# PIClab1.net
KiCad netlist of a schematic drawn in EAGLE
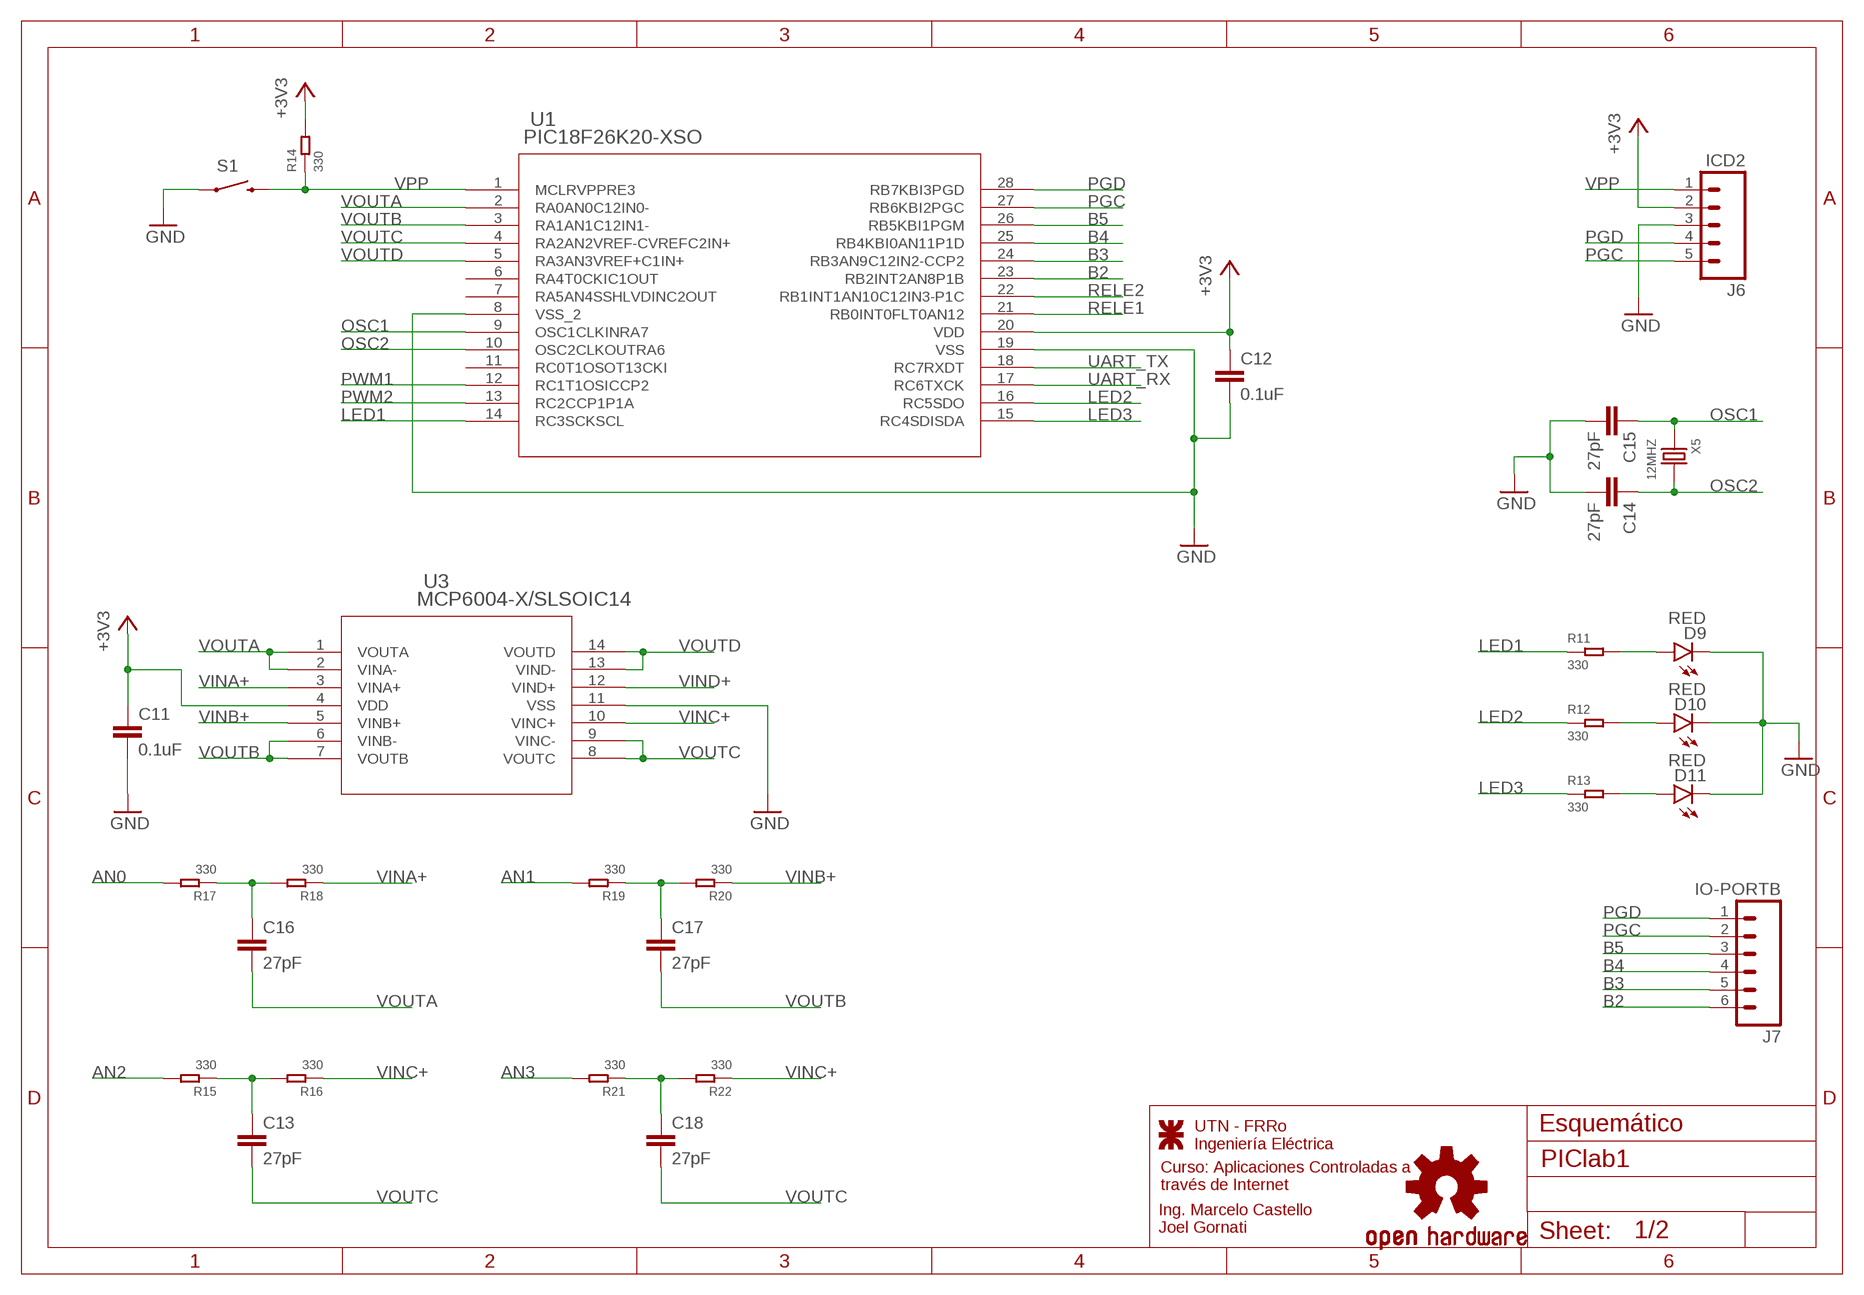
[diagram p0: schematic, sheet 1]
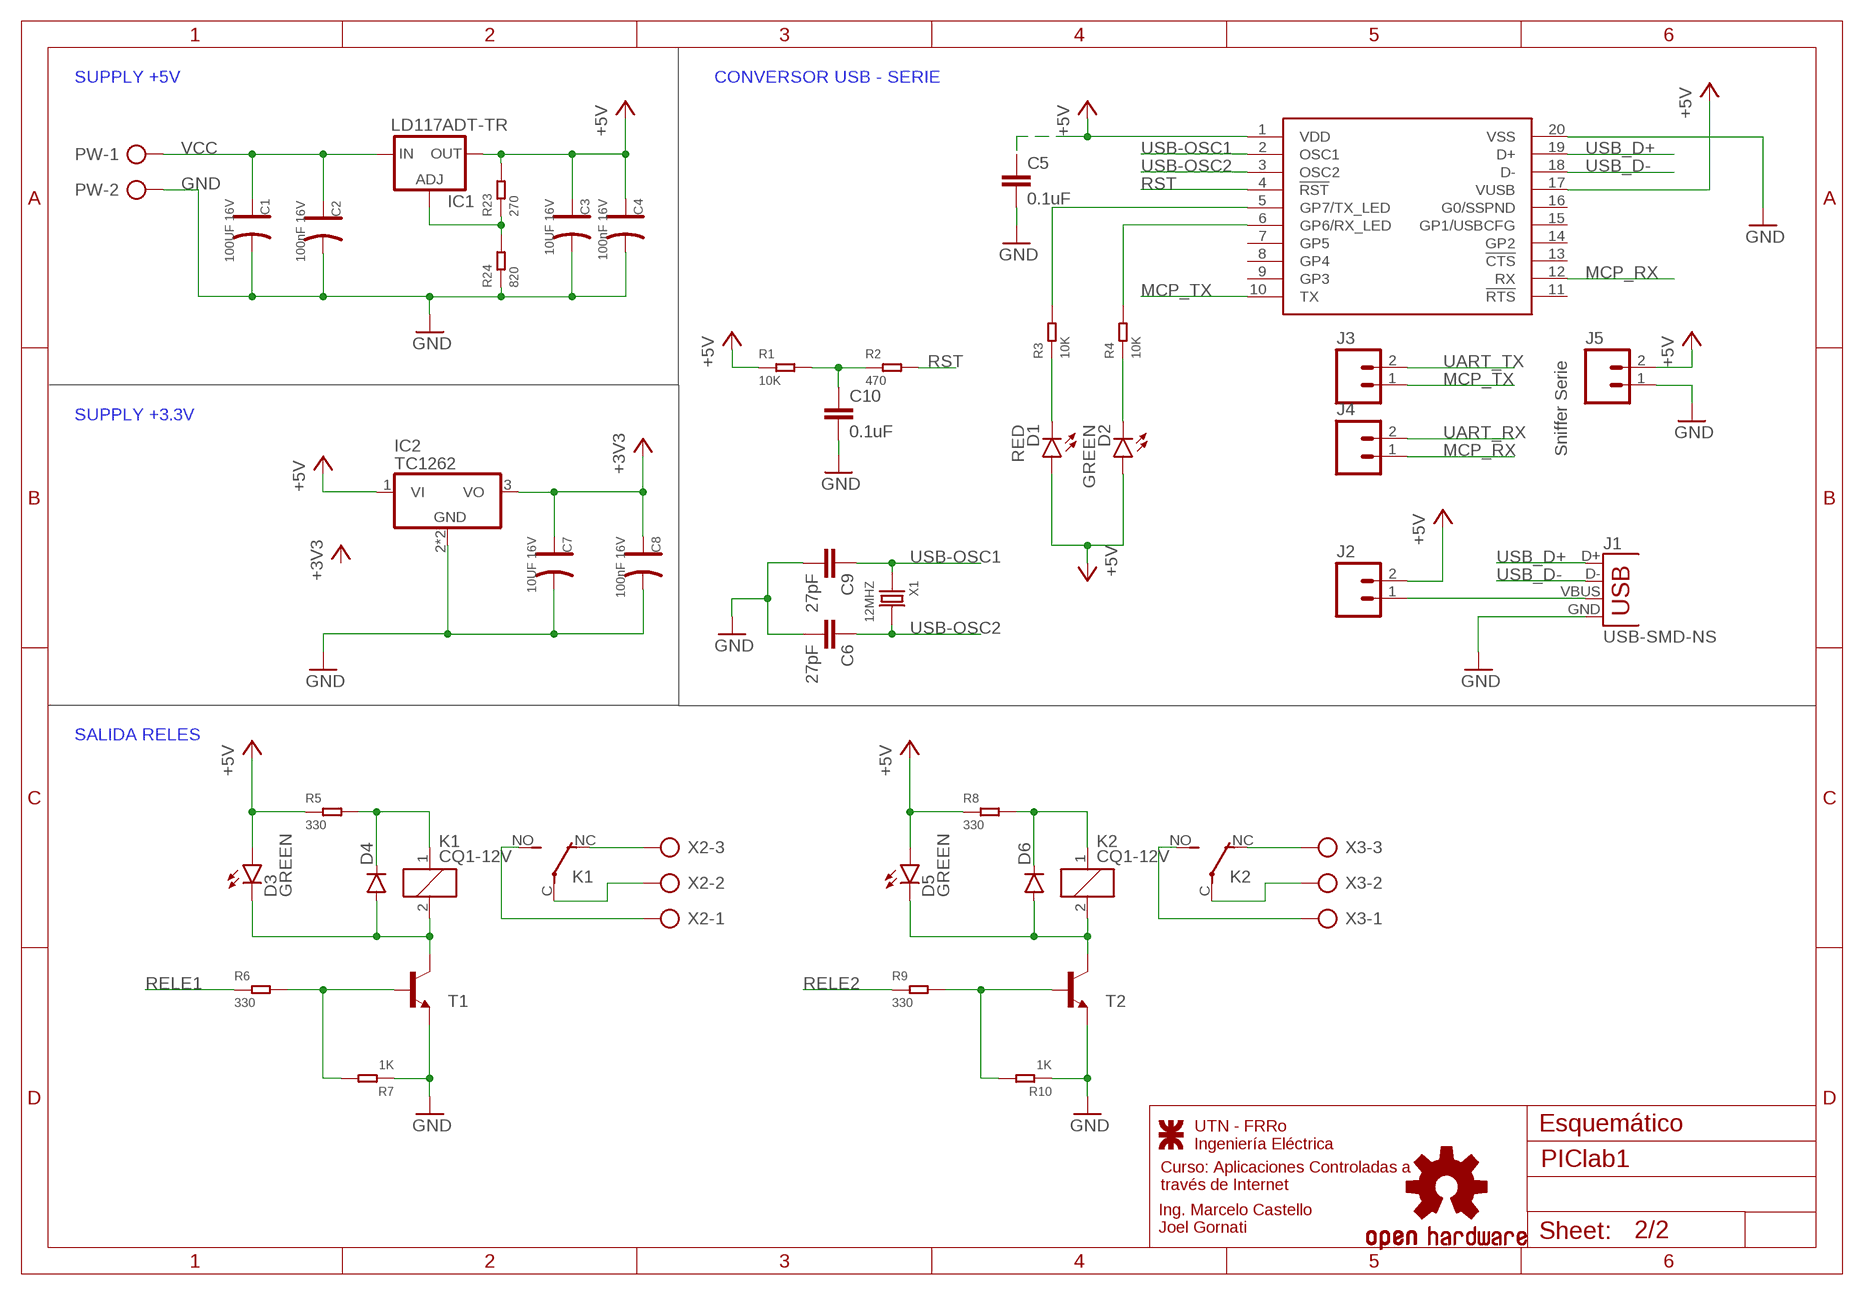
[diagram p1: schematic, sheet 2]

(export (version "E")
  (design (tool "Eeschema 10.0.6"))
  (components
    (comp (ref "C1")
      (value "100UF 16V")
      (footprint "eagle-import:ELECTRO-SMD-A-3.8MM")
      (libsource (lib "eagle-import") (part "ALUMINUM-SMD-10UF-16V"))
    )
    (comp (ref "C2")
      (value "100nF 16V")
      (footprint "eagle-import:ELECTRO-SMD-A-3.8MM")
      (libsource (lib "eagle-import") (part "ALUMINUM-SMD-10UF-16V"))
    )
    (comp (ref "C3")
      (value "10UF 16V")
      (footprint "eagle-import:ELECTRO-SMD-A-3.8MM")
      (libsource (lib "eagle-import") (part "ALUMINUM-SMD-10UF-16V"))
    )
    (comp (ref "C4")
      (value "100nF 16V")
      (footprint "eagle-import:ELECTRO-SMD-A-3.8MM")
      (libsource (lib "eagle-import") (part "ALUMINUM-SMD-10UF-16V"))
    )
    (comp (ref "C5")
      (value "0.1uF")
      (footprint "eagle-import:1206")
      (libsource (lib "eagle-import") (part "CAP1206"))
    )
    (comp (ref "C6")
      (value "27pF")
      (footprint "eagle-import:1206")
      (libsource (lib "eagle-import") (part "CAP1206"))
    )
    (comp (ref "C7")
      (value "10UF 16V")
      (footprint "eagle-import:ELECTRO-SMD-A-3.8MM")
      (libsource (lib "eagle-import") (part "ALUMINUM-SMD-10UF-16V"))
    )
    (comp (ref "C8")
      (value "100nF 16V")
      (footprint "eagle-import:ELECTRO-SMD-A-3.8MM")
      (libsource (lib "eagle-import") (part "ALUMINUM-SMD-10UF-16V"))
    )
    (comp (ref "C9")
      (value "27pF")
      (footprint "eagle-import:1206")
      (libsource (lib "eagle-import") (part "CAP1206"))
    )
    (comp (ref "C10")
      (value "0.1uF")
      (footprint "eagle-import:1206")
      (libsource (lib "eagle-import") (part "CAP1206"))
    )
    (comp (ref "D1")
      (value "RED")
      (footprint "eagle-import:LED-1206")
      (libsource (lib "eagle-import") (part "LED-REDLILYPAD"))
    )
    (comp (ref "D2")
      (value "GREEN")
      (footprint "eagle-import:LED-1206")
      (libsource (lib "eagle-import") (part "LED-REDLILYPAD"))
    )
    (comp (ref "D3")
      (value "GREEN")
      (footprint "eagle-import:LED-1206")
      (libsource (lib "eagle-import") (part "LED-REDLILYPAD"))
    )
    (comp (ref "D4")
      (value "DIODEHV")
      (footprint "eagle-import:DIODE-HV")
      (libsource (lib "eagle-import") (part "DIODEHV"))
    )
    (comp (ref "D5")
      (value "GREEN")
      (footprint "eagle-import:LED-1206")
      (libsource (lib "eagle-import") (part "LED-REDLILYPAD"))
    )
    (comp (ref "D6")
      (value "DIODEHV")
      (footprint "eagle-import:DIODE-HV")
      (libsource (lib "eagle-import") (part "DIODEHV"))
    )
    (comp (ref "IC1")
      (value "LD117ADT-TR")
      (footprint "eagle-import:DPACK")
      (libsource (lib "eagle-import") (part "LD117A?DT-TR"))
    )
    (comp (ref "IC2")
      (value "TC1262")
      (footprint "eagle-import:SOT223")
      (libsource (lib "eagle-import") (part "TC1262"))
    )
    (comp (ref "J1")
      (value "USB-SMD-NS")
      (footprint "eagle-import:USB-MINIB-NOSTOP")
      (libsource (lib "eagle-import") (part "USB-SMD-NS"))
    )
    (comp (ref "J2")
      (value "M02PTH")
      (footprint "eagle-import:1X02")
      (libsource (lib "eagle-import") (part "M02PTH"))
    )
    (comp (ref "J3")
      (value "M02PTH")
      (footprint "eagle-import:1X02")
      (libsource (lib "eagle-import") (part "M02PTH"))
    )
    (comp (ref "J4")
      (value "M02PTH")
      (footprint "eagle-import:1X02")
      (libsource (lib "eagle-import") (part "M02PTH"))
    )
    (comp (ref "J5")
      (value "M02PTH")
      (footprint "eagle-import:1X02")
      (libsource (lib "eagle-import") (part "M02PTH"))
    )
    (comp (ref "K1")
      (value "CQ1-12V")
      (footprint "eagle-import:CQ1")
      (libsource (lib "eagle-import") (part "CQ1-12V"))
    )
    (comp (ref "K2")
      (value "CQ1-12V")
      (footprint "eagle-import:CQ1")
      (libsource (lib "eagle-import") (part "CQ1-12V"))
    )
    (comp (ref "LOGO1")
      (value "OSHW-LOGOMINI")
      (footprint "eagle-import:OSHW-LOGO-MINI")
      (libsource (lib "eagle-import") (part "OSHW-LOGOMINI"))
    )
    (comp (ref "PW")
      (value "AK300/2")
      (footprint "eagle-import:AK300_2")
      (libsource (lib "eagle-import") (part "AK300/2"))
    )
    (comp (ref "R1")
      (value "10K")
      (footprint "eagle-import:R1206")
      (libsource (lib "eagle-import") (part "RES-1206"))
    )
    (comp (ref "R2")
      (value "470")
      (footprint "eagle-import:R1206")
      (libsource (lib "eagle-import") (part "RES-1206"))
    )
    (comp (ref "R3")
      (value "10K")
      (footprint "eagle-import:R1206")
      (libsource (lib "eagle-import") (part "RES-1206"))
    )
    (comp (ref "R4")
      (value "10K")
      (footprint "eagle-import:R1206")
      (libsource (lib "eagle-import") (part "RES-1206"))
    )
    (comp (ref "R5")
      (value "330")
      (footprint "eagle-import:R1206")
      (libsource (lib "eagle-import") (part "RES-1206"))
    )
    (comp (ref "R6")
      (value "330")
      (footprint "eagle-import:R1206")
      (libsource (lib "eagle-import") (part "RES-1206"))
    )
    (comp (ref "R7")
      (value "1K")
      (footprint "eagle-import:R1206")
      (libsource (lib "eagle-import") (part "RES-1206"))
    )
    (comp (ref "R8")
      (value "330")
      (footprint "eagle-import:R1206")
      (libsource (lib "eagle-import") (part "RES-1206"))
    )
    (comp (ref "R9")
      (value "330")
      (footprint "eagle-import:R1206")
      (libsource (lib "eagle-import") (part "RES-1206"))
    )
    (comp (ref "R10")
      (value "1K")
      (footprint "eagle-import:R1206")
      (libsource (lib "eagle-import") (part "RES-1206"))
    )
    (comp (ref "R23")
      (value "270")
      (footprint "eagle-import:R1206")
      (libsource (lib "eagle-import") (part "RES-1206"))
    )
    (comp (ref "R24")
      (value "820")
      (footprint "eagle-import:R1206")
      (libsource (lib "eagle-import") (part "RES-1206"))
    )
    (comp (ref "T1")
      (value "BC817-25-NPN-SOT23-BEC")
      (footprint "eagle-import:SOT23-BEC")
      (libsource (lib "eagle-import") (part "-NPN-SOT23-BECBC817-25"))
    )
    (comp (ref "T2")
      (value "BC817-25-NPN-SOT23-BEC")
      (footprint "eagle-import:SOT23-BEC")
      (libsource (lib "eagle-import") (part "-NPN-SOT23-BECBC817-25"))
    )
    (comp (ref "U$2")
      (value "UTNLOGO")
      (footprint "eagle-import:UTNLOGO")
      (libsource (lib "eagle-import") (part "UTNLOGO"))
    )
    (comp (ref "U2")
      (value "MCP2200SOIC")
      (footprint "eagle-import:MCP2200")
      (libsource (lib "eagle-import") (part "MCP2200SOIC"))
    )
    (comp (ref "X1")
      (value "12MHZ")
      (footprint "eagle-import:HC49UP")
      (libsource (lib "eagle-import") (part "CRYSTAL'HC49UP'"))
    )
    (comp (ref "X2")
      (value "AK500/3")
      (footprint "eagle-import:AK500_3")
      (libsource (lib "eagle-import") (part "AK500/3"))
    )
    (comp (ref "X3")
      (value "AK500/3")
      (footprint "eagle-import:AK500_3")
      (libsource (lib "eagle-import") (part "AK500/3"))
    )
    (comp (ref "C11")
      (value "0.1uF")
      (footprint "eagle-import:1206")
      (libsource (lib "eagle-import") (part "CAP1206"))
    )
    (comp (ref "C12")
      (value "0.1uF")
      (footprint "eagle-import:1206")
      (libsource (lib "eagle-import") (part "CAP1206"))
    )
    (comp (ref "C13")
      (value "27pF")
      (footprint "eagle-import:1206")
      (libsource (lib "eagle-import") (part "CAP1206"))
    )
    (comp (ref "C14")
      (value "27pF")
      (footprint "eagle-import:1206")
      (libsource (lib "eagle-import") (part "CAP1206"))
    )
    (comp (ref "C15")
      (value "27pF")
      (footprint "eagle-import:1206")
      (libsource (lib "eagle-import") (part "CAP1206"))
    )
    (comp (ref "C16")
      (value "27pF")
      (footprint "eagle-import:1206")
      (libsource (lib "eagle-import") (part "CAP1206"))
    )
    (comp (ref "C17")
      (value "27pF")
      (footprint "eagle-import:1206")
      (libsource (lib "eagle-import") (part "CAP1206"))
    )
    (comp (ref "C18")
      (value "27pF")
      (footprint "eagle-import:1206")
      (libsource (lib "eagle-import") (part "CAP1206"))
    )
    (comp (ref "D9")
      (value "RED")
      (footprint "eagle-import:LED-1206")
      (libsource (lib "eagle-import") (part "LED-REDLILYPAD"))
    )
    (comp (ref "D10")
      (value "RED")
      (footprint "eagle-import:LED-1206")
      (libsource (lib "eagle-import") (part "LED-REDLILYPAD"))
    )
    (comp (ref "D11")
      (value "RED")
      (footprint "eagle-import:LED-1206")
      (libsource (lib "eagle-import") (part "LED-REDLILYPAD"))
    )
    (comp (ref "J6")
      (value "ICD2")
      (footprint "eagle-import:1X05")
      (libsource (lib "eagle-import") (part "M05PTH"))
    )
    (comp (ref "J7")
      (value "IO-PORTB")
      (footprint "eagle-import:1X06")
      (libsource (lib "eagle-import") (part "M06SILK_FEMALE_PTH"))
    )
    (comp (ref "LOGO2")
      (value "OSHW-LOGOMINI")
      (footprint "eagle-import:OSHW-LOGO-MINI")
      (libsource (lib "eagle-import") (part "OSHW-LOGOMINI"))
    )
    (comp (ref "R11")
      (value "330")
      (footprint "eagle-import:R1206")
      (libsource (lib "eagle-import") (part "RES-1206"))
    )
    (comp (ref "R12")
      (value "330")
      (footprint "eagle-import:R1206")
      (libsource (lib "eagle-import") (part "RES-1206"))
    )
    (comp (ref "R13")
      (value "330")
      (footprint "eagle-import:R1206")
      (libsource (lib "eagle-import") (part "RES-1206"))
    )
    (comp (ref "R14")
      (value "330")
      (footprint "eagle-import:R1206")
      (libsource (lib "eagle-import") (part "RES-1206"))
    )
    (comp (ref "R15")
      (value "330")
      (footprint "eagle-import:R1206")
      (libsource (lib "eagle-import") (part "RES-1206"))
    )
    (comp (ref "R16")
      (value "330")
      (footprint "eagle-import:R1206")
      (libsource (lib "eagle-import") (part "RES-1206"))
    )
    (comp (ref "R17")
      (value "330")
      (footprint "eagle-import:R1206")
      (libsource (lib "eagle-import") (part "RES-1206"))
    )
    (comp (ref "R18")
      (value "330")
      (footprint "eagle-import:R1206")
      (libsource (lib "eagle-import") (part "RES-1206"))
    )
    (comp (ref "R19")
      (value "330")
      (footprint "eagle-import:R1206")
      (libsource (lib "eagle-import") (part "RES-1206"))
    )
    (comp (ref "R20")
      (value "330")
      (footprint "eagle-import:R1206")
      (libsource (lib "eagle-import") (part "RES-1206"))
    )
    (comp (ref "R21")
      (value "330")
      (footprint "eagle-import:R1206")
      (libsource (lib "eagle-import") (part "RES-1206"))
    )
    (comp (ref "R22")
      (value "330")
      (footprint "eagle-import:R1206")
      (libsource (lib "eagle-import") (part "RES-1206"))
    )
    (comp (ref "S1")
      (value "SWITCH-MOMENTARY-2SMD-4")
      (footprint "eagle-import:TACTILE_SWITCH_TALL")
      (libsource (lib "eagle-import") (part "SWITCH-MOMENTARY-2SMD-4"))
    )
    (comp (ref "U$3")
      (value "UTNLOGO")
      (footprint "eagle-import:UTNLOGO")
      (libsource (lib "eagle-import") (part "UTNLOGO"))
    )
    (comp (ref "U1")
      (value "PIC18F26K20-XSO")
      (footprint "eagle-import:SOIC28-W_MC")
      (libsource (lib "eagle-import") (part "PIC18F26K20-XSO"))
    )
    (comp (ref "U3")
      (value "MCP6004-X/SLSOIC14")
      (footprint "eagle-import:SOIC14-N_MC")
      (libsource (lib "eagle-import") (part "MCP6004-X/SLSOIC14"))
    )
    (comp (ref "X5")
      (value "12MHZ")
      (footprint "eagle-import:HC49UP")
      (libsource (lib "eagle-import") (part "CRYSTAL'HC49UP'"))
    )
  )
  (nets
    (net (code "1") (name "+3V3") (class "Default")
      (node (ref "C11") (pin "1") (pinfunction "1_1") (pintype "passive"))
      (node (ref "C12") (pin "1") (pinfunction "1_1") (pintype "passive"))
      (node (ref "C7") (pin "+") (pinfunction "+_+") (pintype "passive"))
      (node (ref "C8") (pin "+") (pinfunction "+_+") (pintype "passive"))
      (node (ref "IC2") (pin "3") (pinfunction "VO_3") (pintype "passive"))
      (node (ref "J6") (pin "2") (pinfunction "2_2") (pintype "passive"))
      (node (ref "R14") (pin "2") (pinfunction "2_2") (pintype "passive"))
      (node (ref "U1") (pin "20") (pinfunction "VDD_20") (pintype "passive"))
      (node (ref "U3") (pin "4") (pinfunction "VDD_4") (pintype "passive"))
    )
    (net (code "2") (name "+5V") (class "Default")
      (node (ref "C3") (pin "+") (pinfunction "+_+") (pintype "passive"))
      (node (ref "C4") (pin "+") (pinfunction "+_+") (pintype "passive"))
      (node (ref "C5") (pin "1") (pinfunction "1_1") (pintype "passive"))
      (node (ref "D1") (pin "A") (pinfunction "A_A") (pintype "passive"))
      (node (ref "D2") (pin "A") (pinfunction "A_A") (pintype "passive"))
      (node (ref "D3") (pin "A") (pinfunction "A_A") (pintype "passive"))
      (node (ref "D5") (pin "A") (pinfunction "A_A") (pintype "passive"))
      (node (ref "IC1") (pin "4") (pinfunction "OUT_4") (pintype "passive"))
      (node (ref "IC2") (pin "1") (pinfunction "VI_1") (pintype "input"))
      (node (ref "J2") (pin "2") (pinfunction "2_2") (pintype "passive"))
      (node (ref "J5") (pin "2") (pinfunction "2_2") (pintype "passive"))
      (node (ref "R1") (pin "1") (pinfunction "1_1") (pintype "passive"))
      (node (ref "R23") (pin "2") (pinfunction "2_2") (pintype "passive"))
      (node (ref "R5") (pin "1") (pinfunction "1_1") (pintype "passive"))
      (node (ref "R8") (pin "1") (pinfunction "1_1") (pintype "passive"))
      (node (ref "U2") (pin "1") (pinfunction "VDD_1") (pintype "bidirectional"))
      (node (ref "U2") (pin "17") (pinfunction "VUSB_17") (pintype "bidirectional"))
    )
    (net (code "3") (name "AN0") (class "Default")
      (node (ref "R17") (pin "2") (pinfunction "2_2") (pintype "passive"))
    )
    (net (code "4") (name "AN1") (class "Default")
      (node (ref "R19") (pin "2") (pinfunction "2_2") (pintype "passive"))
    )
    (net (code "5") (name "AN2") (class "Default")
      (node (ref "R15") (pin "2") (pinfunction "2_2") (pintype "passive"))
    )
    (net (code "6") (name "AN3") (class "Default")
      (node (ref "R21") (pin "2") (pinfunction "2_2") (pintype "passive"))
    )
    (net (code "7") (name "B2") (class "Default")
      (node (ref "J7") (pin "6") (pinfunction "6_6") (pintype "passive"))
      (node (ref "U1") (pin "23") (pinfunction "RB2INT2AN8P1B_23") (pintype "passive"))
    )
    (net (code "8") (name "B3") (class "Default")
      (node (ref "J7") (pin "5") (pinfunction "5_5") (pintype "passive"))
      (node (ref "U1") (pin "24") (pinfunction "RB3AN9C12IN2-CCP2_24") (pintype "passive"))
    )
    (net (code "9") (name "B4") (class "Default")
      (node (ref "J7") (pin "4") (pinfunction "4_4") (pintype "passive"))
      (node (ref "U1") (pin "25") (pinfunction "RB4KBI0AN11P1D_25") (pintype "passive"))
    )
    (net (code "10") (name "B5") (class "Default")
      (node (ref "J7") (pin "3") (pinfunction "3_3") (pintype "passive"))
      (node (ref "U1") (pin "26") (pinfunction "RB5KBI1PGM_26") (pintype "passive"))
    )
    (net (code "11") (name "GND") (class "Default")
      (node (ref "C1") (pin "-") (pinfunction "-_-") (pintype "passive"))
      (node (ref "C10") (pin "2") (pinfunction "2_2") (pintype "passive"))
      (node (ref "C11") (pin "2") (pinfunction "2_2") (pintype "passive"))
      (node (ref "C12") (pin "2") (pinfunction "2_2") (pintype "passive"))
      (node (ref "C14") (pin "2") (pinfunction "2_2") (pintype "passive"))
      (node (ref "C15") (pin "2") (pinfunction "2_2") (pintype "passive"))
      (node (ref "C2") (pin "-") (pinfunction "-_-") (pintype "passive"))
      (node (ref "C3") (pin "-") (pinfunction "-_-") (pintype "passive"))
      (node (ref "C4") (pin "-") (pinfunction "-_-") (pintype "passive"))
      (node (ref "C5") (pin "2") (pinfunction "2_2") (pintype "passive"))
      (node (ref "C6") (pin "2") (pinfunction "2_2") (pintype "passive"))
      (node (ref "C7") (pin "-") (pinfunction "-_-") (pintype "passive"))
      (node (ref "C8") (pin "-") (pinfunction "-_-") (pintype "passive"))
      (node (ref "C9") (pin "2") (pinfunction "2_2") (pintype "passive"))
      (node (ref "D10") (pin "C") (pinfunction "C_C") (pintype "passive"))
      (node (ref "D11") (pin "C") (pinfunction "C_C") (pintype "passive"))
      (node (ref "D9") (pin "C") (pinfunction "C_C") (pintype "passive"))
      (node (ref "IC2") (pin "2") (pinfunction "GND_2") (pintype "passive"))
      (node (ref "IC2") (pin "4") (pinfunction "GND_4") (pintype "passive"))
      (node (ref "J1") (pin "GND") (pinfunction "GND_GND") (pintype "bidirectional"))
      (node (ref "J5") (pin "1") (pinfunction "1_1") (pintype "passive"))
      (node (ref "J6") (pin "3") (pinfunction "3_3") (pintype "passive"))
      (node (ref "PW") (pin "2") (pinfunction "KL_2") (pintype "passive"))
      (node (ref "R10") (pin "1") (pinfunction "1_1") (pintype "passive"))
      (node (ref "R24") (pin "1") (pinfunction "1_1") (pintype "passive"))
      (node (ref "R7") (pin "1") (pinfunction "1_1") (pintype "passive"))
      (node (ref "S1") (pin "A2") (pinfunction "1_A2") (pintype "passive"))
      (node (ref "T1") (pin "E") (pinfunction "E_E") (pintype "passive"))
      (node (ref "T2") (pin "E") (pinfunction "E_E") (pintype "passive"))
      (node (ref "U1") (pin "19") (pinfunction "VSS_19") (pintype "passive"))
      (node (ref "U1") (pin "8") (pinfunction "VSS_2_8") (pintype "passive"))
      (node (ref "U2") (pin "20") (pinfunction "VSS_20") (pintype "bidirectional"))
      (node (ref "U3") (pin "11") (pinfunction "VSS_11") (pintype "passive"))
    )
    (net (code "12") (name "LED1") (class "Default")
      (node (ref "R11") (pin "1") (pinfunction "1_1") (pintype "passive"))
      (node (ref "U1") (pin "14") (pinfunction "RC3SCKSCL_14") (pintype "passive"))
    )
    (net (code "13") (name "LED2") (class "Default")
      (node (ref "R12") (pin "1") (pinfunction "1_1") (pintype "passive"))
      (node (ref "U1") (pin "16") (pinfunction "RC5SDO_16") (pintype "passive"))
    )
    (net (code "14") (name "LED3") (class "Default")
      (node (ref "R13") (pin "1") (pinfunction "1_1") (pintype "passive"))
      (node (ref "U1") (pin "15") (pinfunction "RC4SDISDA_15") (pintype "passive"))
    )
    (net (code "15") (name "MCP_RX") (class "Default")
      (node (ref "J4") (pin "1") (pinfunction "1_1") (pintype "passive"))
      (node (ref "U2") (pin "12") (pinfunction "RX_12") (pintype "bidirectional"))
    )
    (net (code "16") (name "MCP_TX") (class "Default")
      (node (ref "J3") (pin "1") (pinfunction "1_1") (pintype "passive"))
      (node (ref "U2") (pin "10") (pinfunction "TX_10") (pintype "bidirectional"))
    )
    (net (code "17") (name "Net-(C10-Pad1)") (class "Default")
      (node (ref "C10") (pin "1") (pinfunction "1_1") (pintype "passive"))
      (node (ref "R1") (pin "2") (pinfunction "2_2") (pintype "passive"))
      (node (ref "R2") (pin "1") (pinfunction "1_1") (pintype "passive"))
    )
    (net (code "18") (name "Net-(C13-Pad1)") (class "Default")
      (node (ref "C13") (pin "1") (pinfunction "1_1") (pintype "passive"))
      (node (ref "R15") (pin "1") (pinfunction "1_1") (pintype "passive"))
      (node (ref "R16") (pin "2") (pinfunction "2_2") (pintype "passive"))
    )
    (net (code "19") (name "Net-(C16-Pad1)") (class "Default")
      (node (ref "C16") (pin "1") (pinfunction "1_1") (pintype "passive"))
      (node (ref "R17") (pin "1") (pinfunction "1_1") (pintype "passive"))
      (node (ref "R18") (pin "2") (pinfunction "2_2") (pintype "passive"))
    )
    (net (code "20") (name "Net-(C17-Pad1)") (class "Default")
      (node (ref "C17") (pin "1") (pinfunction "1_1") (pintype "passive"))
      (node (ref "R19") (pin "1") (pinfunction "1_1") (pintype "passive"))
      (node (ref "R20") (pin "2") (pinfunction "2_2") (pintype "passive"))
    )
    (net (code "21") (name "Net-(C18-Pad1)") (class "Default")
      (node (ref "C18") (pin "1") (pinfunction "1_1") (pintype "passive"))
      (node (ref "R21") (pin "1") (pinfunction "1_1") (pintype "passive"))
      (node (ref "R22") (pin "2") (pinfunction "2_2") (pintype "passive"))
    )
    (net (code "22") (name "Net-(D1-PadC)") (class "Default")
      (node (ref "D1") (pin "C") (pinfunction "C_C") (pintype "passive"))
      (node (ref "R3") (pin "1") (pinfunction "1_1") (pintype "passive"))
    )
    (net (code "23") (name "Net-(D2-PadC)") (class "Default")
      (node (ref "D2") (pin "C") (pinfunction "C_C") (pintype "passive"))
      (node (ref "R4") (pin "1") (pinfunction "1_1") (pintype "passive"))
    )
    (net (code "24") (name "Net-(D3-PadC)") (class "Default")
      (node (ref "D3") (pin "C") (pinfunction "C_C") (pintype "passive"))
      (node (ref "D4") (pin "A") (pinfunction "A_A") (pintype "passive"))
      (node (ref "K1") (pin "2") (pinfunction "2_2") (pintype "passive"))
      (node (ref "T1") (pin "C") (pinfunction "C_C") (pintype "passive"))
    )
    (net (code "25") (name "Net-(D4-PadC)") (class "Default")
      (node (ref "D4") (pin "C") (pinfunction "C_C") (pintype "passive"))
      (node (ref "K1") (pin "1") (pinfunction "1_1") (pintype "passive"))
      (node (ref "R5") (pin "2") (pinfunction "2_2") (pintype "passive"))
    )
    (net (code "26") (name "Net-(D5-PadC)") (class "Default")
      (node (ref "D5") (pin "C") (pinfunction "C_C") (pintype "passive"))
      (node (ref "D6") (pin "A") (pinfunction "A_A") (pintype "passive"))
      (node (ref "K2") (pin "2") (pinfunction "2_2") (pintype "passive"))
      (node (ref "T2") (pin "C") (pinfunction "C_C") (pintype "passive"))
    )
    (net (code "27") (name "Net-(D6-PadC)") (class "Default")
      (node (ref "D6") (pin "C") (pinfunction "C_C") (pintype "passive"))
      (node (ref "K2") (pin "1") (pinfunction "1_1") (pintype "passive"))
      (node (ref "R8") (pin "2") (pinfunction "2_2") (pintype "passive"))
    )
    (net (code "28") (name "Net-(D9-PadA)") (class "Default")
      (node (ref "D9") (pin "A") (pinfunction "A_A") (pintype "passive"))
      (node (ref "R11") (pin "2") (pinfunction "2_2") (pintype "passive"))
    )
    (net (code "29") (name "Net-(D10-PadA)") (class "Default")
      (node (ref "D10") (pin "A") (pinfunction "A_A") (pintype "passive"))
      (node (ref "R12") (pin "2") (pinfunction "2_2") (pintype "passive"))
    )
    (net (code "30") (name "Net-(D11-PadA)") (class "Default")
      (node (ref "D11") (pin "A") (pinfunction "A_A") (pintype "passive"))
      (node (ref "R13") (pin "2") (pinfunction "2_2") (pintype "passive"))
    )
    (net (code "31") (name "Net-(IC1-ADJ)") (class "Default")
      (node (ref "IC1") (pin "1") (pinfunction "ADJ_1") (pintype "input"))
      (node (ref "R23") (pin "1") (pinfunction "1_1") (pintype "passive"))
      (node (ref "R24") (pin "2") (pinfunction "2_2") (pintype "passive"))
    )
    (net (code "32") (name "Net-(J1-PadVBUS)") (class "Default")
      (node (ref "J1") (pin "VBUS") (pinfunction "VBUS_VBUS") (pintype "bidirectional"))
      (node (ref "J2") (pin "1") (pinfunction "1_1") (pintype "passive"))
    )
    (net (code "33") (name "Net-(K1B-O)") (class "Default")
      (node (ref "K1") (pin "NC") (pinfunction "O_NC") (pintype "passive"))
      (node (ref "X2") (pin "3") (pinfunction "KL_3") (pintype "passive"))
    )
    (net (code "34") (name "Net-(K1B-P)") (class "Default")
      (node (ref "K1") (pin "C") (pinfunction "P_C") (pintype "passive"))
      (node (ref "X2") (pin "2") (pinfunction "KL_2") (pintype "passive"))
    )
    (net (code "35") (name "Net-(K1B-S)") (class "Default")
      (node (ref "K1") (pin "NO") (pinfunction "S_NO") (pintype "passive"))
      (node (ref "X2") (pin "1") (pinfunction "KL_1") (pintype "passive"))
    )
    (net (code "36") (name "Net-(K2B-O)") (class "Default")
      (node (ref "K2") (pin "NC") (pinfunction "O_NC") (pintype "passive"))
      (node (ref "X3") (pin "3") (pinfunction "KL_3") (pintype "passive"))
    )
    (net (code "37") (name "Net-(K2B-P)") (class "Default")
      (node (ref "K2") (pin "C") (pinfunction "P_C") (pintype "passive"))
      (node (ref "X3") (pin "2") (pinfunction "KL_2") (pintype "passive"))
    )
    (net (code "38") (name "Net-(K2B-S)") (class "Default")
      (node (ref "K2") (pin "NO") (pinfunction "S_NO") (pintype "passive"))
      (node (ref "X3") (pin "1") (pinfunction "KL_1") (pintype "passive"))
    )
    (net (code "39") (name "Net-(R6-Pad2)") (class "Default")
      (node (ref "R6") (pin "2") (pinfunction "2_2") (pintype "passive"))
      (node (ref "R7") (pin "2") (pinfunction "2_2") (pintype "passive"))
      (node (ref "T1") (pin "B") (pinfunction "B_B") (pintype "passive"))
    )
    (net (code "40") (name "Net-(R10-Pad2)") (class "Default")
      (node (ref "R10") (pin "2") (pinfunction "2_2") (pintype "passive"))
      (node (ref "R9") (pin "2") (pinfunction "2_2") (pintype "passive"))
      (node (ref "T2") (pin "B") (pinfunction "B_B") (pintype "passive"))
    )
    (net (code "41") (name "Net-(U2-GP6{slash}RX_LED)") (class "Default")
      (node (ref "R4") (pin "2") (pinfunction "2_2") (pintype "passive"))
      (node (ref "U2") (pin "6") (pinfunction "GP6/RX_LED_6") (pintype "bidirectional"))
    )
    (net (code "42") (name "Net-(U2-GP7{slash}TX_LED)") (class "Default")
      (node (ref "R3") (pin "2") (pinfunction "2_2") (pintype "passive"))
      (node (ref "U2") (pin "5") (pinfunction "GP7/TX_LED_5") (pintype "bidirectional"))
    )
    (net (code "43") (name "OSC1") (class "Default")
      (node (ref "C15") (pin "1") (pinfunction "1_1") (pintype "passive"))
      (node (ref "U1") (pin "9") (pinfunction "OSC1CLKINRA7_9") (pintype "passive"))
      (node (ref "X5") (pin "1") (pinfunction "1_1") (pintype "passive"))
    )
    (net (code "44") (name "OSC2") (class "Default")
      (node (ref "C14") (pin "1") (pinfunction "1_1") (pintype "passive"))
      (node (ref "U1") (pin "10") (pinfunction "OSC2CLKOUTRA6_10") (pintype "passive"))
      (node (ref "X5") (pin "2") (pinfunction "2_2") (pintype "passive"))
    )
    (net (code "45") (name "PGC") (class "Default")
      (node (ref "J6") (pin "5") (pinfunction "5_5") (pintype "passive"))
      (node (ref "J7") (pin "2") (pinfunction "2_2") (pintype "passive"))
      (node (ref "U1") (pin "27") (pinfunction "RB6KBI2PGC_27") (pintype "passive"))
    )
    (net (code "46") (name "PGD") (class "Default")
      (node (ref "J6") (pin "4") (pinfunction "4_4") (pintype "passive"))
      (node (ref "J7") (pin "1") (pinfunction "1_1") (pintype "passive"))
      (node (ref "U1") (pin "28") (pinfunction "RB7KBI3PGD_28") (pintype "passive"))
    )
    (net (code "47") (name "PWM1") (class "Default")
      (node (ref "U1") (pin "12") (pinfunction "RC1T1OSICCP2_12") (pintype "passive"))
    )
    (net (code "48") (name "PWM2") (class "Default")
      (node (ref "U1") (pin "13") (pinfunction "RC2CCP1P1A_13") (pintype "passive"))
    )
    (net (code "49") (name "RELE1") (class "Default")
      (node (ref "R6") (pin "1") (pinfunction "1_1") (pintype "passive"))
      (node (ref "U1") (pin "21") (pinfunction "RB0INT0FLT0AN12_21") (pintype "passive"))
    )
    (net (code "50") (name "RELE2") (class "Default")
      (node (ref "R9") (pin "1") (pinfunction "1_1") (pintype "passive"))
      (node (ref "U1") (pin "22") (pinfunction "RB1INT1AN10C12IN3-P1C_22") (pintype "passive"))
    )
    (net (code "51") (name "RST") (class "Default")
      (node (ref "R2") (pin "2") (pinfunction "2_2") (pintype "passive"))
      (node (ref "U2") (pin "4") (pinfunction "~{RST}_4") (pintype "bidirectional"))
    )
    (net (code "52") (name "UART_RX") (class "Default")
      (node (ref "J4") (pin "2") (pinfunction "2_2") (pintype "passive"))
      (node (ref "U1") (pin "17") (pinfunction "RC6TXCK_17") (pintype "passive"))
    )
    (net (code "53") (name "UART_TX") (class "Default")
      (node (ref "J3") (pin "2") (pinfunction "2_2") (pintype "passive"))
      (node (ref "U1") (pin "18") (pinfunction "RC7RXDT_18") (pintype "passive"))
    )
    (net (code "54") (name "USB-OSC1") (class "Default")
      (node (ref "C9") (pin "1") (pinfunction "1_1") (pintype "passive"))
      (node (ref "U2") (pin "2") (pinfunction "OSC1_2") (pintype "bidirectional"))
      (node (ref "X1") (pin "1") (pinfunction "1_1") (pintype "passive"))
    )
    (net (code "55") (name "USB-OSC2") (class "Default")
      (node (ref "C6") (pin "1") (pinfunction "1_1") (pintype "passive"))
      (node (ref "U2") (pin "3") (pinfunction "OSC2_3") (pintype "bidirectional"))
      (node (ref "X1") (pin "2") (pinfunction "2_2") (pintype "passive"))
    )
    (net (code "56") (name "USB_D+") (class "Default")
      (node (ref "J1") (pin "D+") (pinfunction "D+_D+") (pintype "bidirectional"))
      (node (ref "U2") (pin "19") (pinfunction "D+_19") (pintype "bidirectional"))
    )
    (net (code "57") (name "USB_D-") (class "Default")
      (node (ref "J1") (pin "D-") (pinfunction "D-_D-") (pintype "bidirectional"))
      (node (ref "U2") (pin "18") (pinfunction "D-_18") (pintype "bidirectional"))
    )
    (net (code "58") (name "VCC") (class "Default")
      (node (ref "C1") (pin "+") (pinfunction "+_+") (pintype "passive"))
      (node (ref "C2") (pin "+") (pinfunction "+_+") (pintype "passive"))
      (node (ref "IC1") (pin "3") (pinfunction "IN_3") (pintype "input"))
      (node (ref "PW") (pin "1") (pinfunction "KL_1") (pintype "passive"))
    )
    (net (code "59") (name "VINA+") (class "Default")
      (node (ref "R18") (pin "1") (pinfunction "1_1") (pintype "passive"))
      (node (ref "U3") (pin "3") (pinfunction "VINA+_3") (pintype "passive"))
    )
    (net (code "60") (name "VINB+") (class "Default")
      (node (ref "R20") (pin "1") (pinfunction "1_1") (pintype "passive"))
      (node (ref "U3") (pin "5") (pinfunction "VINB+_5") (pintype "passive"))
    )
    (net (code "61") (name "VINC+") (class "Default")
      (node (ref "R16") (pin "1") (pinfunction "1_1") (pintype "passive"))
      (node (ref "R22") (pin "1") (pinfunction "1_1") (pintype "passive"))
      (node (ref "U3") (pin "10") (pinfunction "VINC+_10") (pintype "passive"))
    )
    (net (code "62") (name "VIND+") (class "Default")
      (node (ref "U3") (pin "12") (pinfunction "VIND+_12") (pintype "passive"))
    )
    (net (code "63") (name "VOUTA") (class "Default")
      (node (ref "C16") (pin "2") (pinfunction "2_2") (pintype "passive"))
      (node (ref "U1") (pin "2") (pinfunction "RA0AN0C12IN0-_2") (pintype "passive"))
      (node (ref "U3") (pin "1") (pinfunction "VOUTA_1") (pintype "passive"))
      (node (ref "U3") (pin "2") (pinfunction "VINA-_2") (pintype "passive"))
    )
    (net (code "64") (name "VOUTB") (class "Default")
      (node (ref "C17") (pin "2") (pinfunction "2_2") (pintype "passive"))
      (node (ref "U1") (pin "3") (pinfunction "RA1AN1C12IN1-_3") (pintype "passive"))
      (node (ref "U3") (pin "6") (pinfunction "VINB-_6") (pintype "passive"))
      (node (ref "U3") (pin "7") (pinfunction "VOUTB_7") (pintype "passive"))
    )
    (net (code "65") (name "VOUTC") (class "Default")
      (node (ref "C13") (pin "2") (pinfunction "2_2") (pintype "passive"))
      (node (ref "C18") (pin "2") (pinfunction "2_2") (pintype "passive"))
      (node (ref "U1") (pin "4") (pinfunction "RA2AN2VREF-CVREFC2IN+_4") (pintype "passive"))
      (node (ref "U3") (pin "8") (pinfunction "VOUTC_8") (pintype "passive"))
      (node (ref "U3") (pin "9") (pinfunction "VINC-_9") (pintype "passive"))
    )
    (net (code "66") (name "VOUTD") (class "Default")
      (node (ref "U1") (pin "5") (pinfunction "RA3AN3VREF+C1IN+_5") (pintype "passive"))
      (node (ref "U3") (pin "13") (pinfunction "VIND-_13") (pintype "passive"))
      (node (ref "U3") (pin "14") (pinfunction "VOUTD_14") (pintype "passive"))
    )
    (net (code "67") (name "VPP") (class "Default")
      (node (ref "J6") (pin "1") (pinfunction "1_1") (pintype "passive"))
      (node (ref "R14") (pin "1") (pinfunction "1_1") (pintype "passive"))
      (node (ref "S1") (pin "B2") (pinfunction "2_B2") (pintype "passive"))
      (node (ref "U1") (pin "1") (pinfunction "MCLRVPPRE3_1") (pintype "passive"))
    )
    (net (code "68") (name "unconnected-(U1-RA4T0CKIC1OUT-Pad6)") (class "Default")
      (node (ref "U1") (pin "6") (pinfunction "RA4T0CKIC1OUT_6") (pintype "passive"))
    )
    (net (code "69") (name "unconnected-(U1-RA5AN4SSHLVDINC2OUT-Pad7)") (class "Default")
      (node (ref "U1") (pin "7") (pinfunction "RA5AN4SSHLVDINC2OUT_7") (pintype "passive"))
    )
    (net (code "70") (name "unconnected-(U1-RC0T1OSOT13CKI-Pad11)") (class "Default")
      (node (ref "U1") (pin "11") (pinfunction "RC0T1OSOT13CKI_11") (pintype "passive"))
    )
    (net (code "71") (name "unconnected-(U2-G0{slash}SSPND-Pad16)") (class "Default")
      (node (ref "U2") (pin "16") (pinfunction "G0/SSPND_16") (pintype "bidirectional"))
    )
    (net (code "72") (name "unconnected-(U2-GP1{slash}USBCFG-Pad15)") (class "Default")
      (node (ref "U2") (pin "15") (pinfunction "GP1/USBCFG_15") (pintype "bidirectional"))
    )
    (net (code "73") (name "unconnected-(U2-GP2-Pad14)") (class "Default")
      (node (ref "U2") (pin "14") (pinfunction "GP2_14") (pintype "bidirectional"))
    )
    (net (code "74") (name "unconnected-(U2-GP3-Pad9)") (class "Default")
      (node (ref "U2") (pin "9") (pinfunction "GP3_9") (pintype "bidirectional"))
    )
    (net (code "75") (name "unconnected-(U2-GP4-Pad8)") (class "Default")
      (node (ref "U2") (pin "8") (pinfunction "GP4_8") (pintype "bidirectional"))
    )
    (net (code "76") (name "unconnected-(U2-GP5-Pad7)") (class "Default")
      (node (ref "U2") (pin "7") (pinfunction "GP5_7") (pintype "bidirectional"))
    )
    (net (code "77") (name "unconnected-(U2-~{CTS}-Pad13)") (class "Default")
      (node (ref "U2") (pin "13") (pinfunction "~{CTS}_13") (pintype "bidirectional"))
    )
    (net (code "78") (name "unconnected-(U2-~{RTS}-Pad11)") (class "Default")
      (node (ref "U2") (pin "11") (pinfunction "~{RTS}_11") (pintype "bidirectional"))
    )
  )
)
